# etapa6.net
KiCad netlist of a schematic drawn in Altium Designer
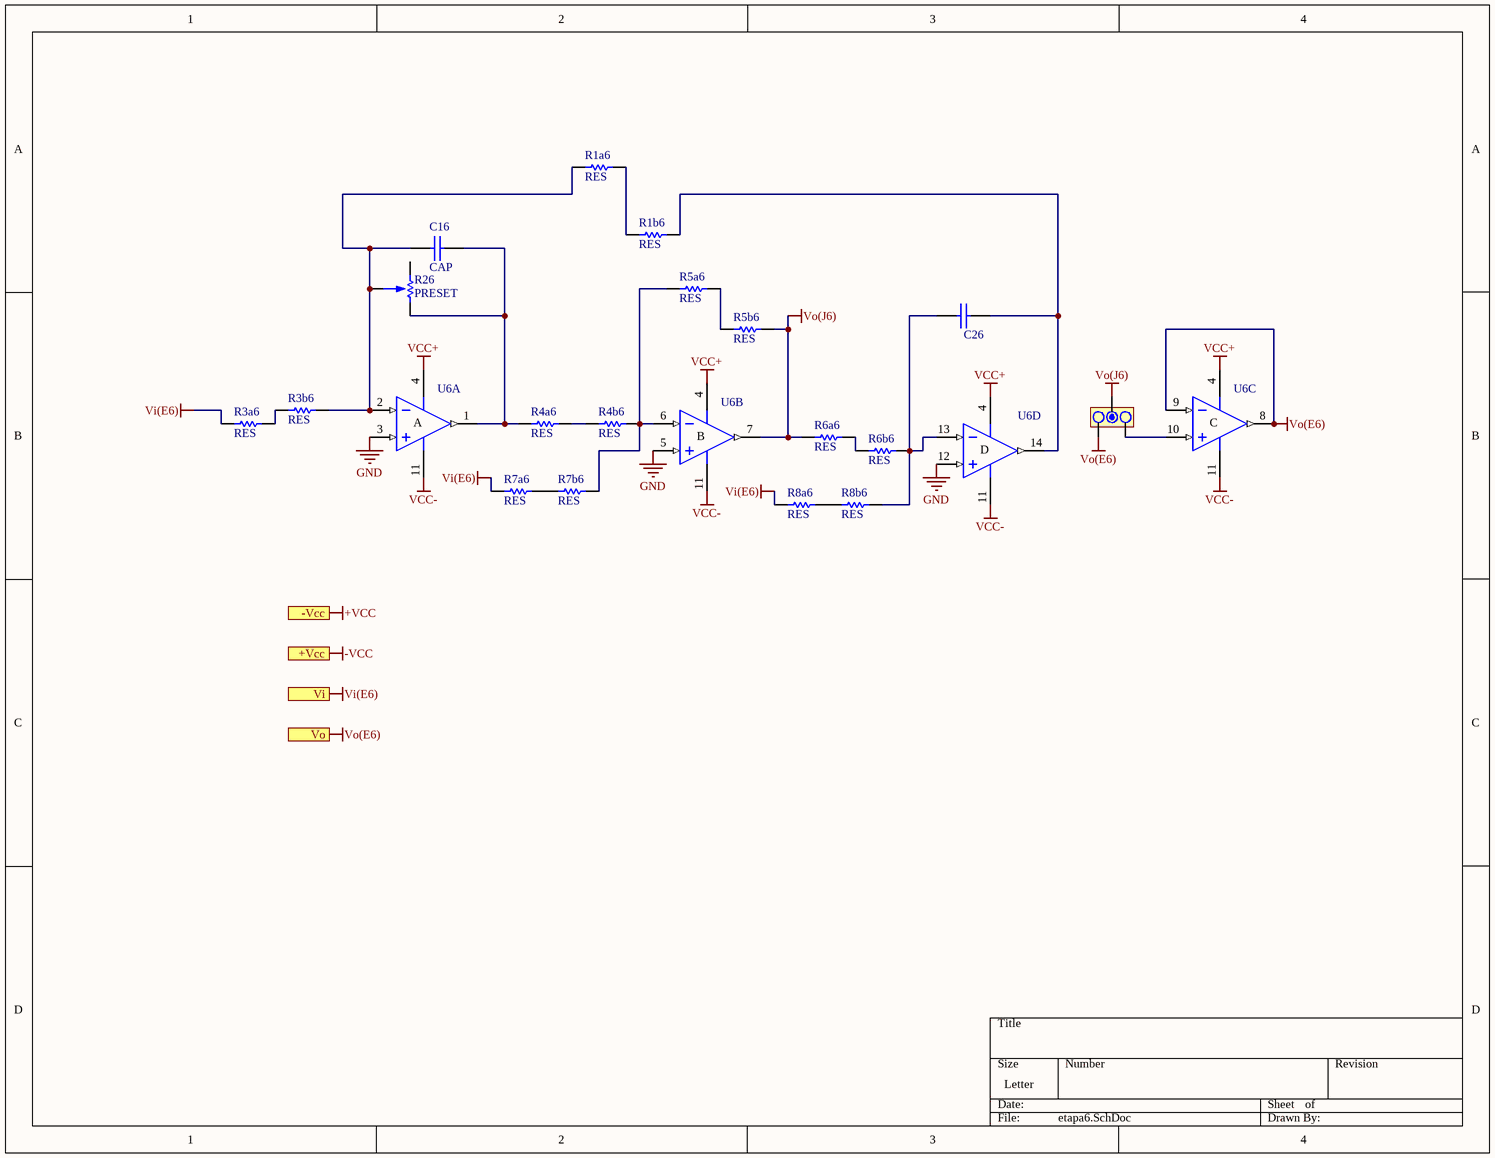
[diagram p0: etapa6.SchDoc]

(export (version "E")
  (design (tool "Eeschema 10.0.6"))
  (components
    (comp (ref "C16") (value "CAP") (footprint "CAP200") (libsource (lib "LIBEBAL") (part "CAP")))
    (comp (ref "C26") (value "CAP") (footprint "CAP200") (libsource (lib "LIBEBAL") (part "CAP")))
    (comp (ref "Jumper6") (value "JUMPER") (footprint "JUMPER3") (libsource (lib "LIBEBAL") (part "JUMPER3")))
    (comp (ref "R1a6") (value "RES") (footprint "0805") (libsource (lib "LIBEBAL") (part "RES")))
    (comp (ref "R1b6") (value "RES") (footprint "0805") (libsource (lib "LIBEBAL") (part "RES")))
    (comp (ref "R3a6") (value "RES") (footprint "0805") (libsource (lib "LIBEBAL") (part "RES")))
    (comp (ref "R3b6") (value "RES") (footprint "0805") (libsource (lib "LIBEBAL") (part "RES")))
    (comp (ref "R4a6") (value "RES") (footprint "0805") (libsource (lib "LIBEBAL") (part "RES")))
    (comp (ref "R4b6") (value "RES") (footprint "0805") (libsource (lib "LIBEBAL") (part "RES")))
    (comp (ref "R5a6") (value "RES") (footprint "0805") (libsource (lib "LIBEBAL") (part "RES")))
    (comp (ref "R5b6") (value "RES") (footprint "0805") (libsource (lib "LIBEBAL") (part "RES")))
    (comp (ref "R6a6") (value "RES") (footprint "0805") (libsource (lib "LIBEBAL") (part "RES")))
    (comp (ref "R6b6") (value "RES") (footprint "0805") (libsource (lib "LIBEBAL") (part "RES")))
    (comp (ref "R7a6") (value "RES") (footprint "0805") (libsource (lib "LIBEBAL") (part "RES")))
    (comp (ref "R7b6") (value "RES") (footprint "0805") (libsource (lib "LIBEBAL") (part "RES")))
    (comp (ref "R8a6") (value "RES") (footprint "0805") (libsource (lib "LIBEBAL") (part "RES")))
    (comp (ref "R8b6") (value "RES") (footprint "0805") (libsource (lib "LIBEBAL") (part "RES")))
    (comp (ref "R26") (value "PRESET") (footprint "PRESET V") (libsource (lib "LIBEBAL") (part "PRESET")))
    (comp (ref "U6")
      (value "TL084N")
      (footprint "N014")
      (description "JFET-Input Operational Amplifier")
      (fields (field (name "PUBLISHER") "Altium Limited"))
      (libsource (lib "TI Operational Amplifier") (part "TL084N"))
    )
  )
  (nets
    (net (code "3") (name "GND") (class "Default")
      (node (ref "U6") (pin "12") (pinfunction "IN+_12") (pintype "input"))
      (node (ref "U6") (pin "3") (pinfunction "IN+_3") (pintype "input"))
      (node (ref "U6") (pin "5") (pinfunction "IN+_5") (pintype "input"))
    )
    (net (code "4") (name "Net-(R1a6-Pad2)") (class "Default")
      (node (ref "R1a6") (pin "2") (pinfunction "2_2") (pintype "passive"))
      (node (ref "R1b6") (pin "1") (pinfunction "1_1") (pintype "passive"))
    )
    (net (code "5") (name "Net-(R3a6-Pad2)") (class "Default")
      (node (ref "R3a6") (pin "2") (pinfunction "2_2") (pintype "passive"))
      (node (ref "R3b6") (pin "1") (pinfunction "1_1") (pintype "passive"))
    )
    (net (code "6") (name "Net-(R4a6-Pad2)") (class "Default")
      (node (ref "R4a6") (pin "2") (pinfunction "2_2") (pintype "passive"))
      (node (ref "R4b6") (pin "1") (pinfunction "1_1") (pintype "passive"))
    )
    (net (code "7") (name "Net-(R5a6-Pad2)") (class "Default")
      (node (ref "R5a6") (pin "2") (pinfunction "2_2") (pintype "passive"))
      (node (ref "R5b6") (pin "1") (pinfunction "1_1") (pintype "passive"))
    )
    (net (code "8") (name "Net-(R6a6-Pad2)") (class "Default")
      (node (ref "R6a6") (pin "2") (pinfunction "2_2") (pintype "passive"))
      (node (ref "R6b6") (pin "1") (pinfunction "1_1") (pintype "passive"))
    )
    (net (code "9") (name "Net-(R7a6-Pad2)") (class "Default")
      (node (ref "R7a6") (pin "2") (pinfunction "2_2") (pintype "passive"))
      (node (ref "R7b6") (pin "1") (pinfunction "1_1") (pintype "passive"))
    )
    (net (code "10") (name "Net-(R8a6-Pad2)") (class "Default")
      (node (ref "R8a6") (pin "2") (pinfunction "2_2") (pintype "passive"))
      (node (ref "R8b6") (pin "1") (pinfunction "1_1") (pintype "passive"))
    )
    (net (code "11") (name "Net-(U6A-IN-)") (class "Default")
      (node (ref "C16") (pin "1") (pinfunction "1_1") (pintype "passive"))
      (node (ref "R1a6") (pin "1") (pinfunction "1_1") (pintype "passive"))
      (node (ref "R26") (pin "2") (pinfunction "2_2") (pintype "passive"))
      (node (ref "R3b6") (pin "2") (pinfunction "2_2") (pintype "passive"))
      (node (ref "U6") (pin "2") (pinfunction "IN-_2") (pintype "input"))
    )
    (net (code "12") (name "Net-(U6A-OUT)") (class "Default")
      (node (ref "C16") (pin "2") (pinfunction "2_2") (pintype "passive"))
      (node (ref "R26") (pin "1") (pinfunction "1_1") (pintype "passive"))
      (node (ref "R4a6") (pin "1") (pinfunction "1_1") (pintype "passive"))
      (node (ref "U6") (pin "1") (pinfunction "OUT_1") (pintype "output"))
    )
    (net (code "13") (name "Net-(U6B-IN-)") (class "Default")
      (node (ref "R4b6") (pin "2") (pinfunction "2_2") (pintype "passive"))
      (node (ref "R5a6") (pin "1") (pinfunction "1_1") (pintype "passive"))
      (node (ref "R7b6") (pin "2") (pinfunction "2_2") (pintype "passive"))
      (node (ref "U6") (pin "6") (pinfunction "IN-_6") (pintype "input"))
    )
    (net (code "14") (name "Net-(U6C-IN+)") (class "Default")
      (node (ref "Jumper6") (pin "1") (pinfunction "1_1") (pintype "passive"))
      (node (ref "U6") (pin "10") (pinfunction "IN+_10") (pintype "input"))
    )
    (net (code "15") (name "Net-(U6D-IN-)") (class "Default")
      (node (ref "C26") (pin "1") (pinfunction "1_1") (pintype "passive"))
      (node (ref "R6b6") (pin "2") (pinfunction "2_2") (pintype "passive"))
      (node (ref "R8b6") (pin "2") (pinfunction "2_2") (pintype "passive"))
      (node (ref "U6") (pin "13") (pinfunction "IN-_13") (pintype "input"))
    )
    (net (code "16") (name "Net-(U6D-OUT)") (class "Default")
      (node (ref "C26") (pin "2") (pinfunction "2_2") (pintype "passive"))
      (node (ref "R1b6") (pin "2") (pinfunction "2_2") (pintype "passive"))
      (node (ref "U6") (pin "14") (pinfunction "OUT_14") (pintype "output"))
    )
    (net (code "17") (name "VCC+") (class "Default")
      (node (ref "U6") (pin "4") (pinfunction "V+_4") (pintype "power_in"))
    )
    (net (code "18") (name "VCC-") (class "Default")
      (node (ref "U6") (pin "11") (pinfunction "V-_11") (pintype "power_in"))
    )
    (net (code "19") (name "Vi(E6)") (class "Default")
      (node (ref "R3a6") (pin "1") (pinfunction "1_1") (pintype "passive"))
      (node (ref "R7a6") (pin "1") (pinfunction "1_1") (pintype "passive"))
      (node (ref "R8a6") (pin "1") (pinfunction "1_1") (pintype "passive"))
    )
    (net (code "20") (name "Vo(E6)") (class "Default")
      (node (ref "Jumper6") (pin "3") (pinfunction "3_3") (pintype "passive"))
      (node (ref "U6") (pin "8") (pinfunction "OUT_8") (pintype "output"))
      (node (ref "U6") (pin "9") (pinfunction "IN-_9") (pintype "input"))
    )
    (net (code "21") (name "Vo(J6)") (class "Default")
      (node (ref "Jumper6") (pin "2") (pinfunction "2_2") (pintype "passive"))
      (node (ref "R5b6") (pin "2") (pinfunction "2_2") (pintype "passive"))
      (node (ref "R6a6") (pin "1") (pinfunction "1_1") (pintype "passive"))
      (node (ref "U6") (pin "7") (pinfunction "OUT_7") (pintype "output"))
    )
    (net (code "22") (name "unconnected-(R26-Pad3)") (class "Default")
      (node (ref "R26") (pin "3") (pinfunction "3_3") (pintype "passive"))
    )
  )
)
